# EPM3032_breakout.net
KiCad netlist of a schematic drawn in Altium Designer
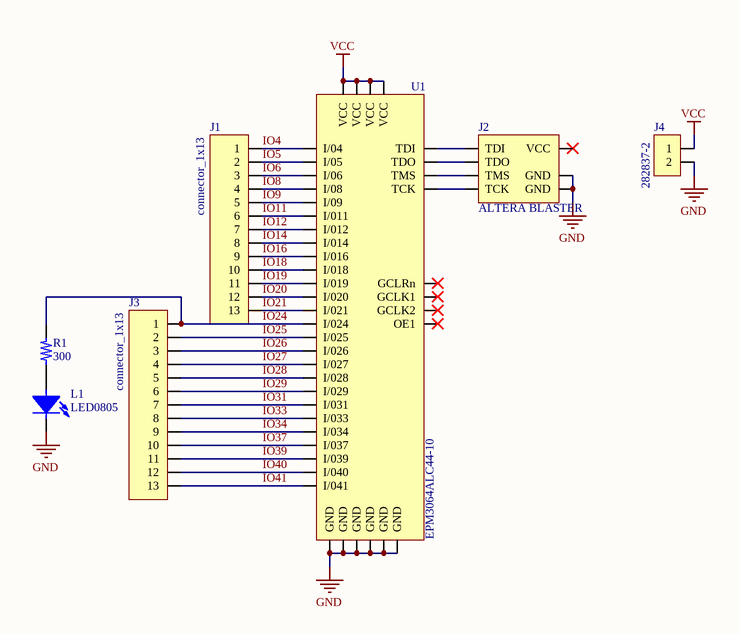
[diagram p0: EPM3032_breakout.SchDoc]

(export (version "E")
  (design (tool "Eeschema 10.0.6"))
  (components
    (comp (ref "J1")
      (value "connector_1x13")
      (footprint "CONECTOR_1X13")
      (libsource (lib "EPM3032_breakout") (part "connector_1x13"))
    )
    (comp (ref "J2")
      (value "ALTERA BLASTER")
      (footprint "ALTERA_BLASTER")
      (libsource (lib "EPM3032_breakout") (part "ALTERA_JTAG"))
    )
    (comp (ref "J3")
      (value "connector_1x13")
      (footprint "CONECTOR_1X13")
      (libsource (lib "EPM3032_breakout") (part "connector_1x13"))
    )
    (comp (ref "J4")
      (value "282837-2")
      (footprint "282837-2")
      (description "Conn Terminal Blocks F 2 POS 5.08mm Solder ST Thru-Hole 13.5A/Contact")
      (fields (field (name "MANUFACTURER") "TE Connectivity") (field (name "VOLTAGE") "300V"))
      (libsource (lib "EPM3032_breakout") (part "282837-2"))
    )
    (comp (ref "L1")
      (value "LED0805")
      (footprint "LED0805")
      (description "LED0805 any color")
      (libsource (lib "EPM3032_breakout") (part "LED0805"))
    )
    (comp (ref "R1") (value "300") (footprint "R0805") (libsource (lib "EPM3032_breakout") (part "R0805")))
    (comp (ref "U1")
      (value "EPM3064ALC44-10")
      (footprint "PLCC44_DIP")
      (description "IC CPLD 64MC 10NS 44PLCC")
      (fields (field (name "MANUFACTURER") "Intel Altera"))
      (libsource (lib "EPM3032_breakout") (part "EPM3064ALC44-10"))
    )
  )
  (nets
    (net (code "1") (name "/IO4") (class "Default")
      (node (ref "J1") (pin "1") (pinfunction "1_1") (pintype "passive"))
      (node (ref "U1") (pin "4") (pinfunction "I/04_4") (pintype "passive"))
    )
    (net (code "2") (name "/IO5") (class "Default")
      (node (ref "J1") (pin "2") (pinfunction "2_2") (pintype "passive"))
      (node (ref "U1") (pin "5") (pinfunction "I/05_5") (pintype "passive"))
    )
    (net (code "3") (name "/IO6") (class "Default")
      (node (ref "J1") (pin "3") (pinfunction "3_3") (pintype "passive"))
      (node (ref "U1") (pin "6") (pinfunction "I/06_6") (pintype "passive"))
    )
    (net (code "4") (name "/IO8") (class "Default")
      (node (ref "J1") (pin "4") (pinfunction "4_4") (pintype "passive"))
      (node (ref "U1") (pin "8") (pinfunction "I/08_8") (pintype "passive"))
    )
    (net (code "5") (name "/IO9") (class "Default")
      (node (ref "J1") (pin "5") (pinfunction "5_5") (pintype "passive"))
      (node (ref "U1") (pin "9") (pinfunction "I/09_9") (pintype "passive"))
    )
    (net (code "6") (name "/IO11") (class "Default")
      (node (ref "J1") (pin "6") (pinfunction "6_6") (pintype "passive"))
      (node (ref "U1") (pin "11") (pinfunction "I/011_11") (pintype "passive"))
    )
    (net (code "7") (name "/IO12") (class "Default")
      (node (ref "J1") (pin "7") (pinfunction "7_7") (pintype "passive"))
      (node (ref "U1") (pin "12") (pinfunction "I/012_12") (pintype "passive"))
    )
    (net (code "8") (name "/IO14") (class "Default")
      (node (ref "J1") (pin "8") (pinfunction "8_8") (pintype "passive"))
      (node (ref "U1") (pin "14") (pinfunction "I/014_14") (pintype "passive"))
    )
    (net (code "9") (name "/IO16") (class "Default")
      (node (ref "J1") (pin "9") (pinfunction "9_9") (pintype "passive"))
      (node (ref "U1") (pin "16") (pinfunction "I/016_16") (pintype "passive"))
    )
    (net (code "10") (name "/IO18") (class "Default")
      (node (ref "J1") (pin "10") (pinfunction "10_10") (pintype "passive"))
      (node (ref "U1") (pin "18") (pinfunction "I/018_18") (pintype "passive"))
    )
    (net (code "11") (name "/IO19") (class "Default")
      (node (ref "J1") (pin "11") (pinfunction "11_11") (pintype "passive"))
      (node (ref "U1") (pin "19") (pinfunction "I/019_19") (pintype "passive"))
    )
    (net (code "12") (name "/IO20") (class "Default")
      (node (ref "J1") (pin "12") (pinfunction "12_12") (pintype "passive"))
      (node (ref "U1") (pin "20") (pinfunction "I/020_20") (pintype "passive"))
    )
    (net (code "13") (name "/IO21") (class "Default")
      (node (ref "J1") (pin "13") (pinfunction "13_13") (pintype "passive"))
      (node (ref "U1") (pin "21") (pinfunction "I/021_21") (pintype "passive"))
    )
    (net (code "14") (name "/IO24") (class "Default")
      (node (ref "J3") (pin "1") (pinfunction "1_1") (pintype "passive"))
      (node (ref "R1") (pin "2") (pinfunction "2_2") (pintype "passive"))
      (node (ref "U1") (pin "24") (pinfunction "I/024_24") (pintype "passive"))
    )
    (net (code "15") (name "/IO25") (class "Default")
      (node (ref "J3") (pin "2") (pinfunction "2_2") (pintype "passive"))
      (node (ref "U1") (pin "25") (pinfunction "I/025_25") (pintype "passive"))
    )
    (net (code "16") (name "/IO26") (class "Default")
      (node (ref "J3") (pin "3") (pinfunction "3_3") (pintype "passive"))
      (node (ref "U1") (pin "26") (pinfunction "I/026_26") (pintype "passive"))
    )
    (net (code "17") (name "/IO27") (class "Default")
      (node (ref "J3") (pin "4") (pinfunction "4_4") (pintype "passive"))
      (node (ref "U1") (pin "27") (pinfunction "I/027_27") (pintype "passive"))
    )
    (net (code "18") (name "/IO28") (class "Default")
      (node (ref "J3") (pin "5") (pinfunction "5_5") (pintype "passive"))
      (node (ref "U1") (pin "28") (pinfunction "I/028_28") (pintype "passive"))
    )
    (net (code "19") (name "/IO29") (class "Default")
      (node (ref "J3") (pin "6") (pinfunction "6_6") (pintype "passive"))
      (node (ref "U1") (pin "29") (pinfunction "I/029_29") (pintype "passive"))
    )
    (net (code "20") (name "/IO31") (class "Default")
      (node (ref "J3") (pin "7") (pinfunction "7_7") (pintype "passive"))
      (node (ref "U1") (pin "31") (pinfunction "I/031_31") (pintype "passive"))
    )
    (net (code "21") (name "/IO33") (class "Default")
      (node (ref "J3") (pin "8") (pinfunction "8_8") (pintype "passive"))
      (node (ref "U1") (pin "33") (pinfunction "I/033_33") (pintype "passive"))
    )
    (net (code "22") (name "/IO34") (class "Default")
      (node (ref "J3") (pin "9") (pinfunction "9_9") (pintype "passive"))
      (node (ref "U1") (pin "34") (pinfunction "I/034_34") (pintype "passive"))
    )
    (net (code "23") (name "/IO37") (class "Default")
      (node (ref "J3") (pin "10") (pinfunction "10_10") (pintype "passive"))
      (node (ref "U1") (pin "37") (pinfunction "I/037_37") (pintype "passive"))
    )
    (net (code "24") (name "/IO39") (class "Default")
      (node (ref "J3") (pin "11") (pinfunction "11_11") (pintype "passive"))
      (node (ref "U1") (pin "39") (pinfunction "I/039_39") (pintype "passive"))
    )
    (net (code "25") (name "/IO40") (class "Default")
      (node (ref "J3") (pin "12") (pinfunction "12_12") (pintype "passive"))
      (node (ref "U1") (pin "40") (pinfunction "I/040_40") (pintype "passive"))
    )
    (net (code "26") (name "/IO41") (class "Default")
      (node (ref "J3") (pin "13") (pinfunction "13_13") (pintype "passive"))
      (node (ref "U1") (pin "41") (pinfunction "I/041_41") (pintype "passive"))
    )
    (net (code "27") (name "GND") (class "Default")
      (node (ref "J2") (pin "10") (pinfunction "GND_10") (pintype "passive"))
      (node (ref "J2") (pin "2") (pinfunction "GND_2") (pintype "passive"))
      (node (ref "J4") (pin "2") (pinfunction "2_2") (pintype "passive"))
      (node (ref "L1") (pin "1") (pinfunction "C_1") (pintype "passive"))
      (node (ref "U1") (pin "10") (pinfunction "GND_10") (pintype "passive"))
      (node (ref "U1") (pin "17") (pinfunction "GND_17") (pintype "passive"))
      (node (ref "U1") (pin "22") (pinfunction "GND_22") (pintype "passive"))
      (node (ref "U1") (pin "30") (pinfunction "GND_30") (pintype "passive"))
      (node (ref "U1") (pin "36") (pinfunction "GND_36") (pintype "passive"))
      (node (ref "U1") (pin "42") (pinfunction "GND_42") (pintype "passive"))
    )
    (net (code "28") (name "Net-(J2-TCK)") (class "Default")
      (node (ref "J2") (pin "1") (pinfunction "TCK_1") (pintype "passive"))
      (node (ref "U1") (pin "32") (pinfunction "TCK_32") (pintype "passive"))
    )
    (net (code "29") (name "Net-(J2-TDI)") (class "Default")
      (node (ref "J2") (pin "9") (pinfunction "TDI_9") (pintype "passive"))
      (node (ref "U1") (pin "7") (pinfunction "TDI_7") (pintype "passive"))
    )
    (net (code "30") (name "Net-(J2-TDO)") (class "Default")
      (node (ref "J2") (pin "3") (pinfunction "TDO_3") (pintype "passive"))
      (node (ref "U1") (pin "38") (pinfunction "TDO_38") (pintype "passive"))
    )
    (net (code "31") (name "Net-(J2-TMS)") (class "Default")
      (node (ref "J2") (pin "5") (pinfunction "TMS_5") (pintype "passive"))
      (node (ref "U1") (pin "13") (pinfunction "TMS_13") (pintype "passive"))
    )
    (net (code "32") (name "Net-(L1-A)") (class "Default")
      (node (ref "L1") (pin "2") (pinfunction "A_2") (pintype "passive"))
      (node (ref "R1") (pin "1") (pinfunction "1_1") (pintype "passive"))
    )
    (net (code "33") (name "VCC") (class "Default")
      (node (ref "J4") (pin "1") (pinfunction "1_1") (pintype "passive"))
      (node (ref "U1") (pin "15") (pinfunction "VCC_15") (pintype "passive"))
      (node (ref "U1") (pin "23") (pinfunction "VCC_23") (pintype "passive"))
      (node (ref "U1") (pin "3") (pinfunction "VCC_3") (pintype "passive"))
      (node (ref "U1") (pin "35") (pinfunction "VCC_35") (pintype "passive"))
    )
    (net (code "34") (name "unconnected-(J2-VCC-Pad4)") (class "Default")
      (node (ref "J2") (pin "4") (pinfunction "VCC_4") (pintype "passive+no_connect"))
    )
    (net (code "35") (name "unconnected-(U1-GCLK1-Pad43)") (class "Default")
      (node (ref "U1") (pin "43") (pinfunction "GCLK1_43") (pintype "passive+no_connect"))
    )
    (net (code "36") (name "unconnected-(U1-GCLK2-Pad2)") (class "Default")
      (node (ref "U1") (pin "2") (pinfunction "GCLK2_2") (pintype "passive+no_connect"))
    )
    (net (code "37") (name "unconnected-(U1-GCLRn-Pad1)") (class "Default")
      (node (ref "U1") (pin "1") (pinfunction "GCLRn_1") (pintype "passive+no_connect"))
    )
    (net (code "38") (name "unconnected-(U1-OE1-Pad44)") (class "Default")
      (node (ref "U1") (pin "44") (pinfunction "OE1_44") (pintype "passive+no_connect"))
    )
  )
)
